# Microcontroller_STM32F101.net
KiCad netlist of a schematic drawn in Altium Designer
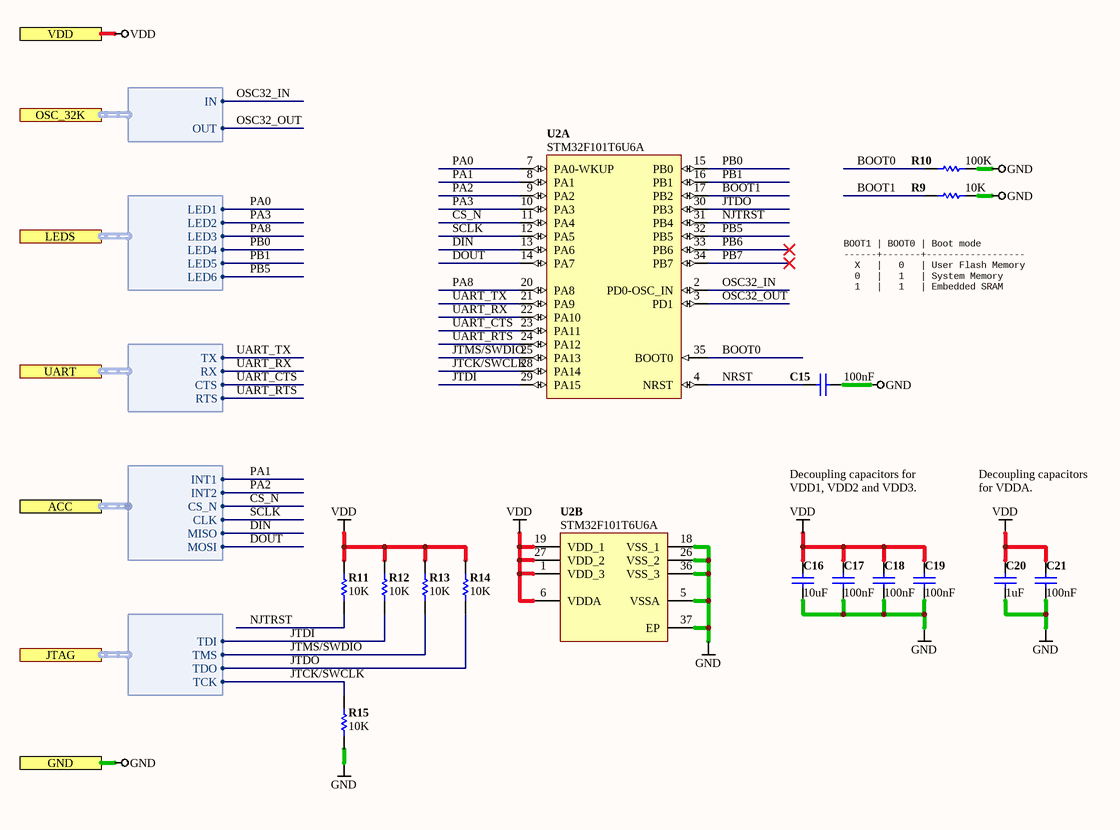
[diagram p0: Microcontroller_STM32F101.SchDoc]

(export (version "E")
  (design (tool "Eeschema 10.0.6"))
  (components
    (comp (ref "C15")
      (value "100nF")
      (footprint "CAPC0402(1005)60_N")
      (description "CAP 100nF 6.3V ±5% 0402 (1005 Metric) Thickness 0.6mm SMD")
      (fields (field (name "TOLERANCE") "±5%") (field (name "Comment") "CAP 100nF 6.3V 0402(1005)"))
      (libsource (lib "Altium Content Vault") (part "CMP-1034-02060-1"))
    )
    (comp (ref "C16")
      (value "10uF")
      (footprint "CAPC0603(1608)100_N")
      (description "CAP 10uF 10V ±20% 0603 (1608 Metric) Thickness 1mm SMD")
      (fields (field (name "TOLERANCE") "±20%") (field (name "Comment") "CAP 10uF 10V 0603(1608)"))
      (libsource (lib "Altium Content Vault") (part "CMP-1035-02800-1"))
    )
    (comp (ref "C17")
      (value "100nF")
      (footprint "CAPC0402(1005)60_N")
      (description "CAP 100nF 6.3V ±5% 0402 (1005 Metric) Thickness 0.6mm SMD")
      (fields (field (name "TOLERANCE") "±5%") (field (name "Comment") "CAP 100nF 6.3V 0402(1005)"))
      (libsource (lib "Altium Content Vault") (part "CMP-1034-02060-1"))
    )
    (comp (ref "C18")
      (value "100nF")
      (footprint "CAPC0402(1005)60_N")
      (description "CAP 100nF 6.3V ±5% 0402 (1005 Metric) Thickness 0.6mm SMD")
      (fields (field (name "TOLERANCE") "±5%") (field (name "Comment") "CAP 100nF 6.3V 0402(1005)"))
      (libsource (lib "Altium Content Vault") (part "CMP-1034-02060-1"))
    )
    (comp (ref "C19")
      (value "100nF")
      (footprint "CAPC0402(1005)60_N")
      (description "CAP 100nF 6.3V ±5% 0402 (1005 Metric) Thickness 0.6mm SMD")
      (fields (field (name "TOLERANCE") "±5%") (field (name "Comment") "CAP 100nF 6.3V 0402(1005)"))
      (libsource (lib "Altium Content Vault") (part "CMP-1034-02060-1"))
    )
    (comp (ref "C20")
      (value "1uF")
      (footprint "CAPC0402(1005)60_N")
      (description "CAP 1uF 6.3V ±10% 0402 (1005 Metric) Thickness 0.6mm SMD")
      (fields (field (name "TOLERANCE") "±10%") (field (name "Comment") "CAP 1uF 6.3V 0402(1005)"))
      (libsource (lib "Altium Content Vault") (part "CMP-1034-02113-1"))
    )
    (comp (ref "C21")
      (value "100nF")
      (footprint "CAPC0402(1005)60_N")
      (description "CAP 100nF 6.3V ±5% 0402 (1005 Metric) Thickness 0.6mm SMD")
      (fields (field (name "TOLERANCE") "±5%") (field (name "Comment") "CAP 100nF 6.3V 0402(1005)"))
      (libsource (lib "Altium Content Vault") (part "CMP-1034-02060-1"))
    )
    (comp (ref "R9")
      (value "10K")
      (footprint "RESC0402(1005)_N")
      (description "10K 0.063W 5% 0402 (1005 Metric)  SMD")
      (fields (field (name "TOLERANCE") "5 %") (field (name "POWER") "0.063 W"))
      (libsource (lib "Altium Content Vault") (part "CMP-1011-00098-1"))
    )
    (comp (ref "R10")
      (value "100K")
      (footprint "RESC0402(1005)_N")
      (description "10K 0.063W 5% 0402 (1005 Metric)  SMD")
      (fields (field (name "TOLERANCE") "5 %") (field (name "POWER") "0.063 W"))
      (libsource (lib "Altium Content Vault") (part "CMP-1011-00098-1"))
    )
    (comp (ref "R11")
      (value "10K")
      (footprint "RESC0402(1005)_N")
      (description "10K 0.063W 5% 0402 (1005 Metric)  SMD")
      (fields (field (name "TOLERANCE") "5 %") (field (name "POWER") "0.063 W"))
      (libsource (lib "Altium Content Vault") (part "CMP-1011-00098-1"))
    )
    (comp (ref "R12")
      (value "10K")
      (footprint "RESC0402(1005)_N")
      (description "10K 0.063W 5% 0402 (1005 Metric)  SMD")
      (fields (field (name "TOLERANCE") "5 %") (field (name "POWER") "0.063 W"))
      (libsource (lib "Altium Content Vault") (part "CMP-1011-00098-1"))
    )
    (comp (ref "R13")
      (value "10K")
      (footprint "RESC0402(1005)_N")
      (description "10K 0.063W 5% 0402 (1005 Metric)  SMD")
      (fields (field (name "TOLERANCE") "5 %") (field (name "POWER") "0.063 W"))
      (libsource (lib "Altium Content Vault") (part "CMP-1011-00098-1"))
    )
    (comp (ref "R14")
      (value "10K")
      (footprint "RESC0402(1005)_N")
      (description "10K 0.063W 5% 0402 (1005 Metric)  SMD")
      (fields (field (name "TOLERANCE") "5 %") (field (name "POWER") "0.063 W"))
      (libsource (lib "Altium Content Vault") (part "CMP-1011-00098-1"))
    )
    (comp (ref "R15")
      (value "10K")
      (footprint "RESC0402(1005)_N")
      (description "10K 0.063W 5% 0402 (1005 Metric)  SMD")
      (fields (field (name "TOLERANCE") "5 %") (field (name "POWER") "0.063 W"))
      (libsource (lib "Altium Content Vault") (part "CMP-1011-00098-1"))
    )
    (comp (ref "U2")
      (value "STM32F101T6U6A")
      (footprint "VFQFPN36_N")
      (libsource (lib "Altium Content Vault") (part "MC-ARM-STM32F101-SQ37"))
    )
  )
  (nets
    (net (code "6") (name "/BOOT0") (class "Default")
      (node (ref "R10") (pin "1") (pinfunction "1_1") (pintype "passive"))
      (node (ref "U2") (pin "35") (pinfunction "BOOT0_35") (pintype "input"))
    )
    (net (code "7") (name "/BOOT1") (class "Default")
      (node (ref "R9") (pin "1") (pinfunction "1_1") (pintype "passive"))
      (node (ref "U2") (pin "17") (pinfunction "PB2_17") (pintype "bidirectional"))
    )
    (net (code "8") (name "/CS_N") (class "Default")
      (node (ref "U2") (pin "11") (pinfunction "PA4_11") (pintype "bidirectional"))
    )
    (net (code "9") (name "/DIN") (class "Default")
      (node (ref "U2") (pin "13") (pinfunction "PA6_13") (pintype "bidirectional"))
    )
    (net (code "10") (name "/DOUT") (class "Default")
      (node (ref "U2") (pin "14") (pinfunction "PA7_14") (pintype "bidirectional"))
    )
    (net (code "11") (name "/JTCK{slash}SWCLK") (class "Default")
      (node (ref "R15") (pin "2") (pinfunction "2_2") (pintype "passive"))
      (node (ref "U2") (pin "28") (pinfunction "PA14_28") (pintype "bidirectional"))
    )
    (net (code "12") (name "/JTDI") (class "Default")
      (node (ref "R12") (pin "1") (pinfunction "1_1") (pintype "passive"))
      (node (ref "U2") (pin "29") (pinfunction "PA15_29") (pintype "bidirectional"))
    )
    (net (code "13") (name "/JTDO") (class "Default")
      (node (ref "R14") (pin "1") (pinfunction "1_1") (pintype "passive"))
      (node (ref "U2") (pin "30") (pinfunction "PB3_30") (pintype "bidirectional"))
    )
    (net (code "14") (name "/JTMS{slash}SWDIO") (class "Default")
      (node (ref "R13") (pin "1") (pinfunction "1_1") (pintype "passive"))
      (node (ref "U2") (pin "25") (pinfunction "PA13_25") (pintype "bidirectional"))
    )
    (net (code "15") (name "/NJTRST") (class "Default")
      (node (ref "R11") (pin "1") (pinfunction "1_1") (pintype "passive"))
      (node (ref "U2") (pin "31") (pinfunction "PB4_31") (pintype "bidirectional"))
    )
    (net (code "16") (name "/NRST") (class "Default")
      (node (ref "C15") (pin "1") (pinfunction "1_1") (pintype "passive"))
      (node (ref "U2") (pin "4") (pinfunction "NRST_4") (pintype "bidirectional"))
    )
    (net (code "17") (name "/OSC32_IN") (class "Default")
      (node (ref "U2") (pin "2") (pinfunction "PD0-OSC_IN_2") (pintype "bidirectional"))
    )
    (net (code "18") (name "/OSC32_OUT") (class "Default")
      (node (ref "U2") (pin "3") (pinfunction "PD1_3") (pintype "bidirectional"))
    )
    (net (code "19") (name "/PA0") (class "Default")
      (node (ref "U2") (pin "7") (pinfunction "PA0-WKUP_7") (pintype "bidirectional"))
    )
    (net (code "20") (name "/PA1") (class "Default")
      (node (ref "U2") (pin "8") (pinfunction "PA1_8") (pintype "bidirectional"))
    )
    (net (code "21") (name "/PA2") (class "Default")
      (node (ref "U2") (pin "9") (pinfunction "PA2_9") (pintype "bidirectional"))
    )
    (net (code "22") (name "/PA3") (class "Default")
      (node (ref "U2") (pin "10") (pinfunction "PA3_10") (pintype "bidirectional"))
    )
    (net (code "23") (name "/PA8") (class "Default")
      (node (ref "U2") (pin "20") (pinfunction "PA8_20") (pintype "bidirectional"))
    )
    (net (code "24") (name "/PB0") (class "Default")
      (node (ref "U2") (pin "15") (pinfunction "PB0_15") (pintype "bidirectional"))
    )
    (net (code "25") (name "/PB1") (class "Default")
      (node (ref "U2") (pin "16") (pinfunction "PB1_16") (pintype "bidirectional"))
    )
    (net (code "26") (name "/PB5") (class "Default")
      (node (ref "U2") (pin "32") (pinfunction "PB5_32") (pintype "bidirectional"))
    )
    (net (code "27") (name "/PB6") (class "Default")
      (node (ref "U2") (pin "33") (pinfunction "PB6_33") (pintype "bidirectional+no_connect"))
    )
    (net (code "28") (name "/PB7") (class "Default")
      (node (ref "U2") (pin "34") (pinfunction "PB7_34") (pintype "bidirectional+no_connect"))
    )
    (net (code "29") (name "/SCLK") (class "Default")
      (node (ref "U2") (pin "12") (pinfunction "PA5_12") (pintype "bidirectional"))
    )
    (net (code "30") (name "/UART_CTS") (class "Default")
      (node (ref "U2") (pin "23") (pinfunction "PA11_23") (pintype "bidirectional"))
    )
    (net (code "31") (name "/UART_RTS") (class "Default")
      (node (ref "U2") (pin "24") (pinfunction "PA12_24") (pintype "bidirectional"))
    )
    (net (code "32") (name "/UART_RX") (class "Default")
      (node (ref "U2") (pin "22") (pinfunction "PA10_22") (pintype "bidirectional"))
    )
    (net (code "33") (name "/UART_TX") (class "Default")
      (node (ref "U2") (pin "21") (pinfunction "PA9_21") (pintype "bidirectional"))
    )
    (net (code "39") (name "GND") (class "Default")
      (node (ref "C15") (pin "2") (pinfunction "2_2") (pintype "passive"))
      (node (ref "C16") (pin "1") (pinfunction "1_1") (pintype "passive"))
      (node (ref "C17") (pin "1") (pinfunction "1_1") (pintype "passive"))
      (node (ref "C18") (pin "1") (pinfunction "1_1") (pintype "passive"))
      (node (ref "C19") (pin "1") (pinfunction "1_1") (pintype "passive"))
      (node (ref "C20") (pin "1") (pinfunction "1_1") (pintype "passive"))
      (node (ref "C21") (pin "1") (pinfunction "1_1") (pintype "passive"))
      (node (ref "R10") (pin "2") (pinfunction "2_2") (pintype "passive"))
      (node (ref "R15") (pin "1") (pinfunction "1_1") (pintype "passive"))
      (node (ref "R9") (pin "2") (pinfunction "2_2") (pintype "passive"))
      (node (ref "U2") (pin "18") (pinfunction "VSS_1_18") (pintype "power_in"))
      (node (ref "U2") (pin "26") (pinfunction "VSS_2_26") (pintype "power_in"))
      (node (ref "U2") (pin "36") (pinfunction "VSS_3_36") (pintype "power_in"))
      (node (ref "U2") (pin "37") (pinfunction "EP_37") (pintype "power_in"))
      (node (ref "U2") (pin "5") (pinfunction "VSSA_5") (pintype "power_in"))
    )
    (net (code "40") (name "VDD") (class "Default")
      (node (ref "C16") (pin "2") (pinfunction "2_2") (pintype "passive"))
      (node (ref "C17") (pin "2") (pinfunction "2_2") (pintype "passive"))
      (node (ref "C18") (pin "2") (pinfunction "2_2") (pintype "passive"))
      (node (ref "C19") (pin "2") (pinfunction "2_2") (pintype "passive"))
      (node (ref "C20") (pin "2") (pinfunction "2_2") (pintype "passive"))
      (node (ref "C21") (pin "2") (pinfunction "2_2") (pintype "passive"))
      (node (ref "R11") (pin "2") (pinfunction "2_2") (pintype "passive"))
      (node (ref "R12") (pin "2") (pinfunction "2_2") (pintype "passive"))
      (node (ref "R13") (pin "2") (pinfunction "2_2") (pintype "passive"))
      (node (ref "R14") (pin "2") (pinfunction "2_2") (pintype "passive"))
      (node (ref "U2") (pin "1") (pinfunction "VDD_3_1") (pintype "power_in"))
      (node (ref "U2") (pin "19") (pinfunction "VDD_1_19") (pintype "power_in"))
      (node (ref "U2") (pin "27") (pinfunction "VDD_2_27") (pintype "power_in"))
      (node (ref "U2") (pin "6") (pinfunction "VDDA_6") (pintype "power_in"))
    )
  )
)
